# lite-board.net
KiCad netlist of a schematic drawn in EAGLE
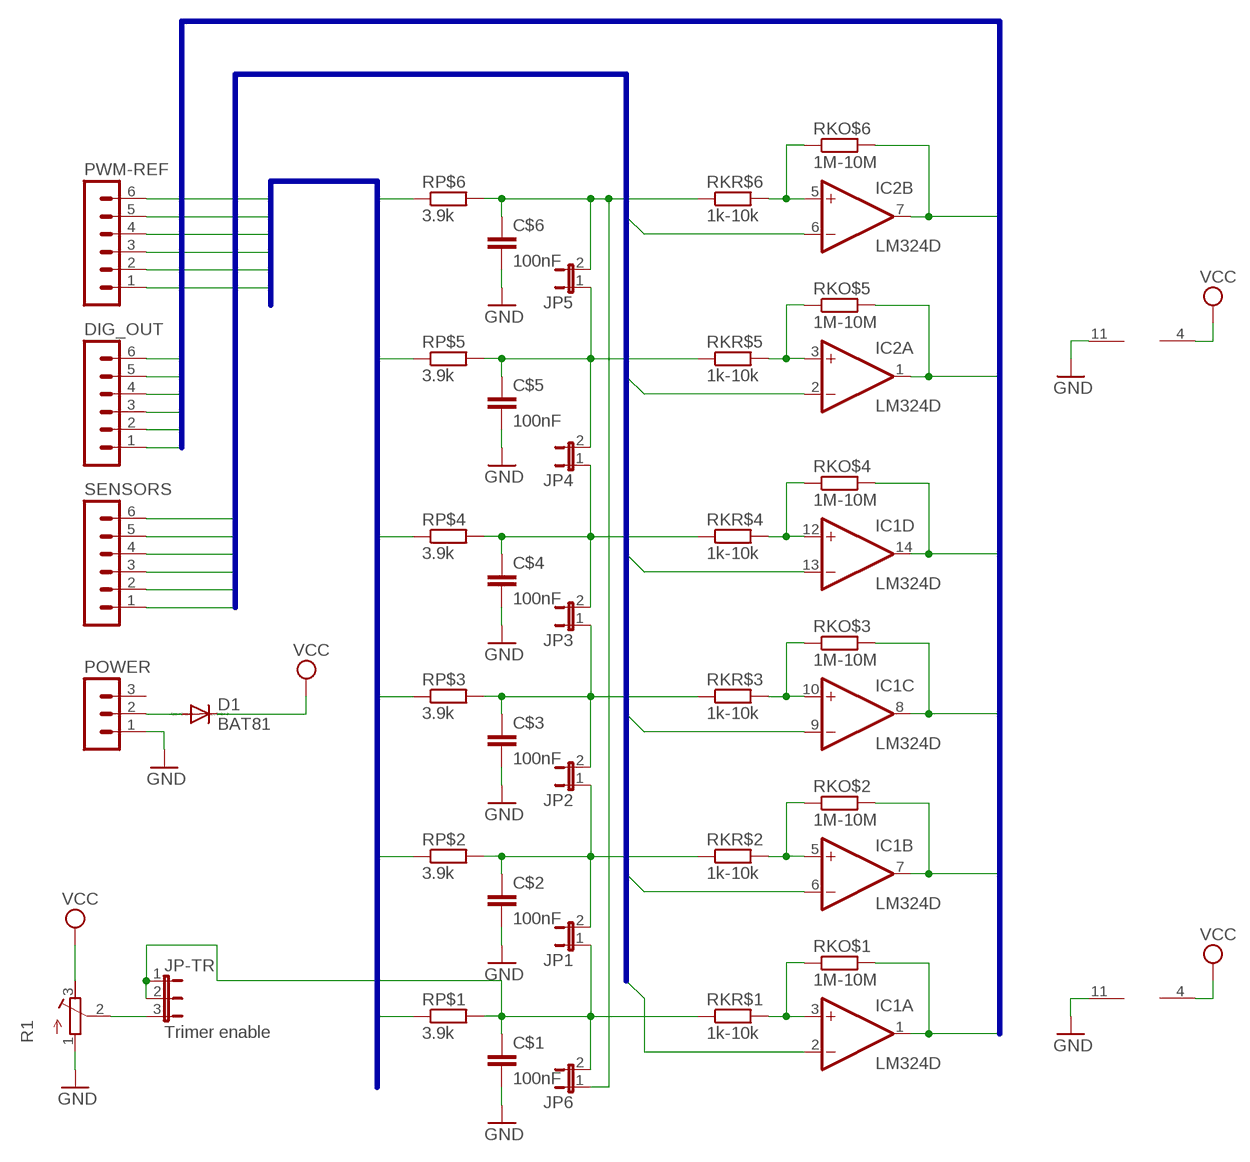
[diagram p0: schematic, sheet 1]

(export (version "E")
  (design (tool "Eeschema 10.0.6"))
  (components
    (comp (ref "C$1")
      (value "100nF")
      (footprint "eagle-import:C025-030X050")
      (libsource (lib "eagle-import") (part "C-EU025-030X050"))
    )
    (comp (ref "C$2")
      (value "100nF")
      (footprint "eagle-import:C025-030X050")
      (libsource (lib "eagle-import") (part "C-EU025-030X050"))
    )
    (comp (ref "C$3")
      (value "100nF")
      (footprint "eagle-import:C025-030X050")
      (libsource (lib "eagle-import") (part "C-EU025-030X050"))
    )
    (comp (ref "C$4")
      (value "100nF")
      (footprint "eagle-import:C025-030X050")
      (libsource (lib "eagle-import") (part "C-EU025-030X050"))
    )
    (comp (ref "C$5")
      (value "100nF")
      (footprint "eagle-import:C025-030X050")
      (libsource (lib "eagle-import") (part "C-EU025-030X050"))
    )
    (comp (ref "C$6")
      (value "100nF")
      (footprint "eagle-import:C025-030X050")
      (libsource (lib "eagle-import") (part "C-EU025-030X050"))
    )
    (comp (ref "D1")
      (value "BAT81")
      (footprint "eagle-import:DO34-7")
      (libsource (lib "eagle-import") (part "BAT81"))
    )
    (comp (ref "DIG_OUT")
      (value "MA06-1")
      (footprint "eagle-import:MA06-1")
      (libsource (lib "eagle-import") (part "MA06-1"))
    )
    (comp (ref "IC1")
      (value "LM324D")
      (footprint "eagle-import:SO14")
      (libsource (lib "eagle-import") (part "LM324D"))
    )
    (comp (ref "IC2")
      (value "LM324D")
      (footprint "eagle-import:SO14")
      (libsource (lib "eagle-import") (part "LM324D"))
    )
    (comp (ref "JP-TR")
      (value "Trimer enable")
      (footprint "eagle-import:JP2")
      (libsource (lib "eagle-import") (part "JP2E"))
    )
    (comp (ref "JP1")
      (value "JP1E")
      (footprint "eagle-import:JP1")
      (libsource (lib "eagle-import") (part "JP1E"))
    )
    (comp (ref "JP2")
      (value "JP1E")
      (footprint "eagle-import:JP1")
      (libsource (lib "eagle-import") (part "JP1E"))
    )
    (comp (ref "JP3")
      (value "JP1E")
      (footprint "eagle-import:JP1")
      (libsource (lib "eagle-import") (part "JP1E"))
    )
    (comp (ref "JP4")
      (value "JP1E")
      (footprint "eagle-import:JP1")
      (libsource (lib "eagle-import") (part "JP1E"))
    )
    (comp (ref "JP5")
      (value "JP1E")
      (footprint "eagle-import:JP1")
      (libsource (lib "eagle-import") (part "JP1E"))
    )
    (comp (ref "JP6")
      (value "JP1E")
      (footprint "eagle-import:JP1")
      (libsource (lib "eagle-import") (part "JP1E"))
    )
    (comp (ref "POWER")
      (value "MA03-1")
      (footprint "eagle-import:MA03-1")
      (libsource (lib "eagle-import") (part "MA03-1"))
    )
    (comp (ref "PWM-REF")
      (value "MA06-1")
      (footprint "eagle-import:MA06-1")
      (libsource (lib "eagle-import") (part "MA06-1"))
    )
    (comp (ref "R1")
      (value "R-TRIMM3296Y")
      (footprint "eagle-import:RTRIM3296Y")
      (libsource (lib "eagle-import") (part "R-TRIMM3296Y"))
    )
    (comp (ref "RKO$1")
      (value "1M-10M")
      (footprint "eagle-import:0204_7")
      (libsource (lib "eagle-import") (part "resistor_R-EU_0204/7"))
    )
    (comp (ref "RKO$2")
      (value "1M-10M")
      (footprint "eagle-import:0204_7")
      (libsource (lib "eagle-import") (part "resistor_R-EU_0204/7"))
    )
    (comp (ref "RKO$3")
      (value "1M-10M")
      (footprint "eagle-import:0204_7")
      (libsource (lib "eagle-import") (part "resistor_R-EU_0204/7"))
    )
    (comp (ref "RKO$4")
      (value "1M-10M")
      (footprint "eagle-import:0204_7")
      (libsource (lib "eagle-import") (part "resistor_R-EU_0204/7"))
    )
    (comp (ref "RKO$5")
      (value "1M-10M")
      (footprint "eagle-import:0204_7")
      (libsource (lib "eagle-import") (part "resistor_R-EU_0204/7"))
    )
    (comp (ref "RKO$6")
      (value "1M-10M")
      (footprint "eagle-import:0204_7")
      (libsource (lib "eagle-import") (part "resistor_R-EU_0204/7"))
    )
    (comp (ref "RKR$1")
      (value "1k-10k")
      (footprint "eagle-import:0204_7")
      (libsource (lib "eagle-import") (part "resistor_R-EU_0204/7"))
    )
    (comp (ref "RKR$2")
      (value "1k-10k")
      (footprint "eagle-import:0204_7")
      (libsource (lib "eagle-import") (part "resistor_R-EU_0204/7"))
    )
    (comp (ref "RKR$3")
      (value "1k-10k")
      (footprint "eagle-import:0204_7")
      (libsource (lib "eagle-import") (part "resistor_R-EU_0204/7"))
    )
    (comp (ref "RKR$4")
      (value "1k-10k")
      (footprint "eagle-import:0204_7")
      (libsource (lib "eagle-import") (part "resistor_R-EU_0204/7"))
    )
    (comp (ref "RKR$5")
      (value "1k-10k")
      (footprint "eagle-import:0204_7")
      (libsource (lib "eagle-import") (part "resistor_R-EU_0204/7"))
    )
    (comp (ref "RKR$6")
      (value "1k-10k")
      (footprint "eagle-import:0204_7")
      (libsource (lib "eagle-import") (part "resistor_R-EU_0204/7"))
    )
    (comp (ref "RP$1")
      (value "3.9k")
      (footprint "eagle-import:0204_7")
      (libsource (lib "eagle-import") (part "R-EU_0204/7"))
    )
    (comp (ref "RP$2")
      (value "3.9k")
      (footprint "eagle-import:0204_7")
      (libsource (lib "eagle-import") (part "R-EU_0204/7"))
    )
    (comp (ref "RP$3")
      (value "3.9k")
      (footprint "eagle-import:0204_7")
      (libsource (lib "eagle-import") (part "R-EU_0204/7"))
    )
    (comp (ref "RP$4")
      (value "3.9k")
      (footprint "eagle-import:0204_7")
      (libsource (lib "eagle-import") (part "R-EU_0204/7"))
    )
    (comp (ref "RP$5")
      (value "3.9k")
      (footprint "eagle-import:0204_7")
      (libsource (lib "eagle-import") (part "R-EU_0204/7"))
    )
    (comp (ref "RP$6")
      (value "3.9k")
      (footprint "eagle-import:0204_7")
      (libsource (lib "eagle-import") (part "R-EU_0204/7"))
    )
    (comp (ref "SENSORS")
      (value "MA06-1")
      (footprint "eagle-import:MA06-1")
      (libsource (lib "eagle-import") (part "MA06-1"))
    )
  )
  (nets
    (net (code "1") (name "/BOUT1") (class "Default")
      (node (ref "DIG_OUT") (pin "1") (pinfunction "1_1") (pintype "passive"))
      (node (ref "IC1") (pin "1") (pinfunction "OUT_1") (pintype "output"))
      (node (ref "RKO$1") (pin "2") (pinfunction "2_2") (pintype "passive"))
    )
    (net (code "2") (name "/BOUT2") (class "Default")
      (node (ref "DIG_OUT") (pin "2") (pinfunction "2_2") (pintype "passive"))
      (node (ref "IC1") (pin "7") (pinfunction "OUT_7") (pintype "output"))
      (node (ref "RKO$2") (pin "2") (pinfunction "2_2") (pintype "passive"))
    )
    (net (code "3") (name "/BOUT3") (class "Default")
      (node (ref "DIG_OUT") (pin "3") (pinfunction "3_3") (pintype "passive"))
      (node (ref "IC1") (pin "8") (pinfunction "OUT_8") (pintype "output"))
      (node (ref "RKO$3") (pin "2") (pinfunction "2_2") (pintype "passive"))
    )
    (net (code "4") (name "/BOUT4") (class "Default")
      (node (ref "DIG_OUT") (pin "4") (pinfunction "4_4") (pintype "passive"))
      (node (ref "IC1") (pin "14") (pinfunction "OUT_14") (pintype "output"))
      (node (ref "RKO$4") (pin "2") (pinfunction "2_2") (pintype "passive"))
    )
    (net (code "5") (name "/BOUT5") (class "Default")
      (node (ref "DIG_OUT") (pin "5") (pinfunction "5_5") (pintype "passive"))
      (node (ref "IC2") (pin "1") (pinfunction "OUT_1") (pintype "output"))
      (node (ref "RKO$5") (pin "2") (pinfunction "2_2") (pintype "passive"))
    )
    (net (code "6") (name "/BOUT6") (class "Default")
      (node (ref "DIG_OUT") (pin "6") (pinfunction "6_6") (pintype "passive"))
      (node (ref "IC2") (pin "7") (pinfunction "OUT_7") (pintype "output"))
      (node (ref "RKO$6") (pin "2") (pinfunction "2_2") (pintype "passive"))
    )
    (net (code "7") (name "/BSENZ1") (class "Default")
      (node (ref "IC1") (pin "2") (pinfunction "-IN_2") (pintype "input"))
      (node (ref "SENSORS") (pin "1") (pinfunction "1_1") (pintype "passive"))
    )
    (net (code "8") (name "/BSENZ2") (class "Default")
      (node (ref "IC1") (pin "6") (pinfunction "-IN_6") (pintype "input"))
      (node (ref "SENSORS") (pin "2") (pinfunction "2_2") (pintype "passive"))
    )
    (net (code "9") (name "/BSENZ3") (class "Default")
      (node (ref "IC1") (pin "9") (pinfunction "-IN_9") (pintype "input"))
      (node (ref "SENSORS") (pin "3") (pinfunction "3_3") (pintype "passive"))
    )
    (net (code "10") (name "/BSENZ4") (class "Default")
      (node (ref "IC1") (pin "13") (pinfunction "-IN_13") (pintype "input"))
      (node (ref "SENSORS") (pin "4") (pinfunction "4_4") (pintype "passive"))
    )
    (net (code "11") (name "/BSENZ5") (class "Default")
      (node (ref "IC2") (pin "2") (pinfunction "-IN_2") (pintype "input"))
      (node (ref "SENSORS") (pin "5") (pinfunction "5_5") (pintype "passive"))
    )
    (net (code "12") (name "/BSENZ6") (class "Default")
      (node (ref "IC2") (pin "6") (pinfunction "-IN_6") (pintype "input"))
      (node (ref "SENSORS") (pin "6") (pinfunction "6_6") (pintype "passive"))
    )
    (net (code "13") (name "/REF1") (class "Default")
      (node (ref "PWM-REF") (pin "1") (pinfunction "1_1") (pintype "passive"))
      (node (ref "RP$1") (pin "1") (pinfunction "1_1") (pintype "passive"))
    )
    (net (code "14") (name "/REF2") (class "Default")
      (node (ref "PWM-REF") (pin "2") (pinfunction "2_2") (pintype "passive"))
      (node (ref "RP$2") (pin "1") (pinfunction "1_1") (pintype "passive"))
    )
    (net (code "15") (name "/REF3") (class "Default")
      (node (ref "PWM-REF") (pin "3") (pinfunction "3_3") (pintype "passive"))
      (node (ref "RP$3") (pin "1") (pinfunction "1_1") (pintype "passive"))
    )
    (net (code "16") (name "/REF4") (class "Default")
      (node (ref "PWM-REF") (pin "4") (pinfunction "4_4") (pintype "passive"))
      (node (ref "RP$4") (pin "1") (pinfunction "1_1") (pintype "passive"))
    )
    (net (code "17") (name "/REF5") (class "Default")
      (node (ref "PWM-REF") (pin "5") (pinfunction "5_5") (pintype "passive"))
      (node (ref "RP$5") (pin "1") (pinfunction "1_1") (pintype "passive"))
    )
    (net (code "18") (name "/REF6") (class "Default")
      (node (ref "PWM-REF") (pin "6") (pinfunction "6_6") (pintype "passive"))
      (node (ref "RP$6") (pin "1") (pinfunction "1_1") (pintype "passive"))
    )
    (net (code "19") (name "GND") (class "Default")
      (node (ref "C$1") (pin "2") (pinfunction "2_2") (pintype "passive"))
      (node (ref "C$2") (pin "2") (pinfunction "2_2") (pintype "passive"))
      (node (ref "C$3") (pin "2") (pinfunction "2_2") (pintype "passive"))
      (node (ref "C$4") (pin "2") (pinfunction "2_2") (pintype "passive"))
      (node (ref "C$5") (pin "2") (pinfunction "2_2") (pintype "passive"))
      (node (ref "C$6") (pin "2") (pinfunction "2_2") (pintype "passive"))
      (node (ref "IC1") (pin "11") (pinfunction "V-_11") (pintype "power_in"))
      (node (ref "IC2") (pin "11") (pinfunction "V-_11") (pintype "power_in"))
      (node (ref "POWER") (pin "1") (pinfunction "1_1") (pintype "passive"))
      (node (ref "R1") (pin "1") (pinfunction "E_1") (pintype "passive"))
    )
    (net (code "20") (name "Net-(C$1-Pad1)") (class "Default")
      (node (ref "C$1") (pin "1") (pinfunction "1_1") (pintype "passive"))
      (node (ref "JP-TR") (pin "1") (pinfunction "1_1") (pintype "passive"))
      (node (ref "JP-TR") (pin "2") (pinfunction "2_2") (pintype "passive"))
      (node (ref "JP1") (pin "1") (pinfunction "1_1") (pintype "passive"))
      (node (ref "JP6") (pin "2") (pinfunction "2_2") (pintype "passive"))
      (node (ref "RKR$1") (pin "1") (pinfunction "1_1") (pintype "passive"))
      (node (ref "RP$1") (pin "2") (pinfunction "2_2") (pintype "passive"))
    )
    (net (code "21") (name "Net-(C$2-Pad1)") (class "Default")
      (node (ref "C$2") (pin "1") (pinfunction "1_1") (pintype "passive"))
      (node (ref "JP1") (pin "2") (pinfunction "2_2") (pintype "passive"))
      (node (ref "JP2") (pin "1") (pinfunction "1_1") (pintype "passive"))
      (node (ref "RKR$2") (pin "1") (pinfunction "1_1") (pintype "passive"))
      (node (ref "RP$2") (pin "2") (pinfunction "2_2") (pintype "passive"))
    )
    (net (code "22") (name "Net-(C$3-Pad1)") (class "Default")
      (node (ref "C$3") (pin "1") (pinfunction "1_1") (pintype "passive"))
      (node (ref "JP2") (pin "2") (pinfunction "2_2") (pintype "passive"))
      (node (ref "JP3") (pin "1") (pinfunction "1_1") (pintype "passive"))
      (node (ref "RKR$3") (pin "1") (pinfunction "1_1") (pintype "passive"))
      (node (ref "RP$3") (pin "2") (pinfunction "2_2") (pintype "passive"))
    )
    (net (code "23") (name "Net-(C$4-Pad1)") (class "Default")
      (node (ref "C$4") (pin "1") (pinfunction "1_1") (pintype "passive"))
      (node (ref "JP3") (pin "2") (pinfunction "2_2") (pintype "passive"))
      (node (ref "JP4") (pin "1") (pinfunction "1_1") (pintype "passive"))
      (node (ref "RKR$4") (pin "1") (pinfunction "1_1") (pintype "passive"))
      (node (ref "RP$4") (pin "2") (pinfunction "2_2") (pintype "passive"))
    )
    (net (code "24") (name "Net-(C$5-Pad1)") (class "Default")
      (node (ref "C$5") (pin "1") (pinfunction "1_1") (pintype "passive"))
      (node (ref "JP4") (pin "2") (pinfunction "2_2") (pintype "passive"))
      (node (ref "JP5") (pin "1") (pinfunction "1_1") (pintype "passive"))
      (node (ref "RKR$5") (pin "1") (pinfunction "1_1") (pintype "passive"))
      (node (ref "RP$5") (pin "2") (pinfunction "2_2") (pintype "passive"))
    )
    (net (code "25") (name "Net-(C$6-Pad1)") (class "Default")
      (node (ref "C$6") (pin "1") (pinfunction "1_1") (pintype "passive"))
      (node (ref "JP5") (pin "2") (pinfunction "2_2") (pintype "passive"))
      (node (ref "JP6") (pin "1") (pinfunction "1_1") (pintype "passive"))
      (node (ref "RKR$6") (pin "1") (pinfunction "1_1") (pintype "passive"))
      (node (ref "RP$6") (pin "2") (pinfunction "2_2") (pintype "passive"))
    )
    (net (code "26") (name "Net-(D1-PadA)") (class "Default")
      (node (ref "D1") (pin "A") (pinfunction "A_A") (pintype "passive"))
      (node (ref "POWER") (pin "2") (pinfunction "2_2") (pintype "passive"))
    )
    (net (code "27") (name "Net-(IC1A-+IN)") (class "Default")
      (node (ref "IC1") (pin "3") (pinfunction "+IN_3") (pintype "input"))
      (node (ref "RKO$1") (pin "1") (pinfunction "1_1") (pintype "passive"))
      (node (ref "RKR$1") (pin "2") (pinfunction "2_2") (pintype "passive"))
    )
    (net (code "28") (name "Net-(IC1B-+IN)") (class "Default")
      (node (ref "IC1") (pin "5") (pinfunction "+IN_5") (pintype "input"))
      (node (ref "RKO$2") (pin "1") (pinfunction "1_1") (pintype "passive"))
      (node (ref "RKR$2") (pin "2") (pinfunction "2_2") (pintype "passive"))
    )
    (net (code "29") (name "Net-(IC1C-+IN)") (class "Default")
      (node (ref "IC1") (pin "10") (pinfunction "+IN_10") (pintype "input"))
      (node (ref "RKO$3") (pin "1") (pinfunction "1_1") (pintype "passive"))
      (node (ref "RKR$3") (pin "2") (pinfunction "2_2") (pintype "passive"))
    )
    (net (code "30") (name "Net-(IC1D-+IN)") (class "Default")
      (node (ref "IC1") (pin "12") (pinfunction "+IN_12") (pintype "input"))
      (node (ref "RKO$4") (pin "1") (pinfunction "1_1") (pintype "passive"))
      (node (ref "RKR$4") (pin "2") (pinfunction "2_2") (pintype "passive"))
    )
    (net (code "31") (name "Net-(IC2A-+IN)") (class "Default")
      (node (ref "IC2") (pin "3") (pinfunction "+IN_3") (pintype "input"))
      (node (ref "RKO$5") (pin "1") (pinfunction "1_1") (pintype "passive"))
      (node (ref "RKR$5") (pin "2") (pinfunction "2_2") (pintype "passive"))
    )
    (net (code "32") (name "Net-(IC2B-+IN)") (class "Default")
      (node (ref "IC2") (pin "5") (pinfunction "+IN_5") (pintype "input"))
      (node (ref "RKO$6") (pin "1") (pinfunction "1_1") (pintype "passive"))
      (node (ref "RKR$6") (pin "2") (pinfunction "2_2") (pintype "passive"))
    )
    (net (code "33") (name "Net-(R1-S)") (class "Default")
      (node (ref "JP-TR") (pin "3") (pinfunction "3_3") (pintype "passive"))
      (node (ref "R1") (pin "2") (pinfunction "S_2") (pintype "passive"))
    )
    (net (code "34") (name "VCC") (class "Default")
      (node (ref "D1") (pin "C") (pinfunction "C_C") (pintype "passive"))
      (node (ref "IC1") (pin "4") (pinfunction "V+_4") (pintype "power_in"))
      (node (ref "IC2") (pin "4") (pinfunction "V+_4") (pintype "power_in"))
      (node (ref "R1") (pin "3") (pinfunction "A_3") (pintype "passive"))
    )
    (net (code "35") (name "unconnected-(POWER-Pad3)") (class "Default")
      (node (ref "POWER") (pin "3") (pinfunction "3_3") (pintype "passive"))
    )
  )
)
